# mLRS-tx-dualSx-top-v031.net
KiCad netlist of a schematic drawn in EAGLE
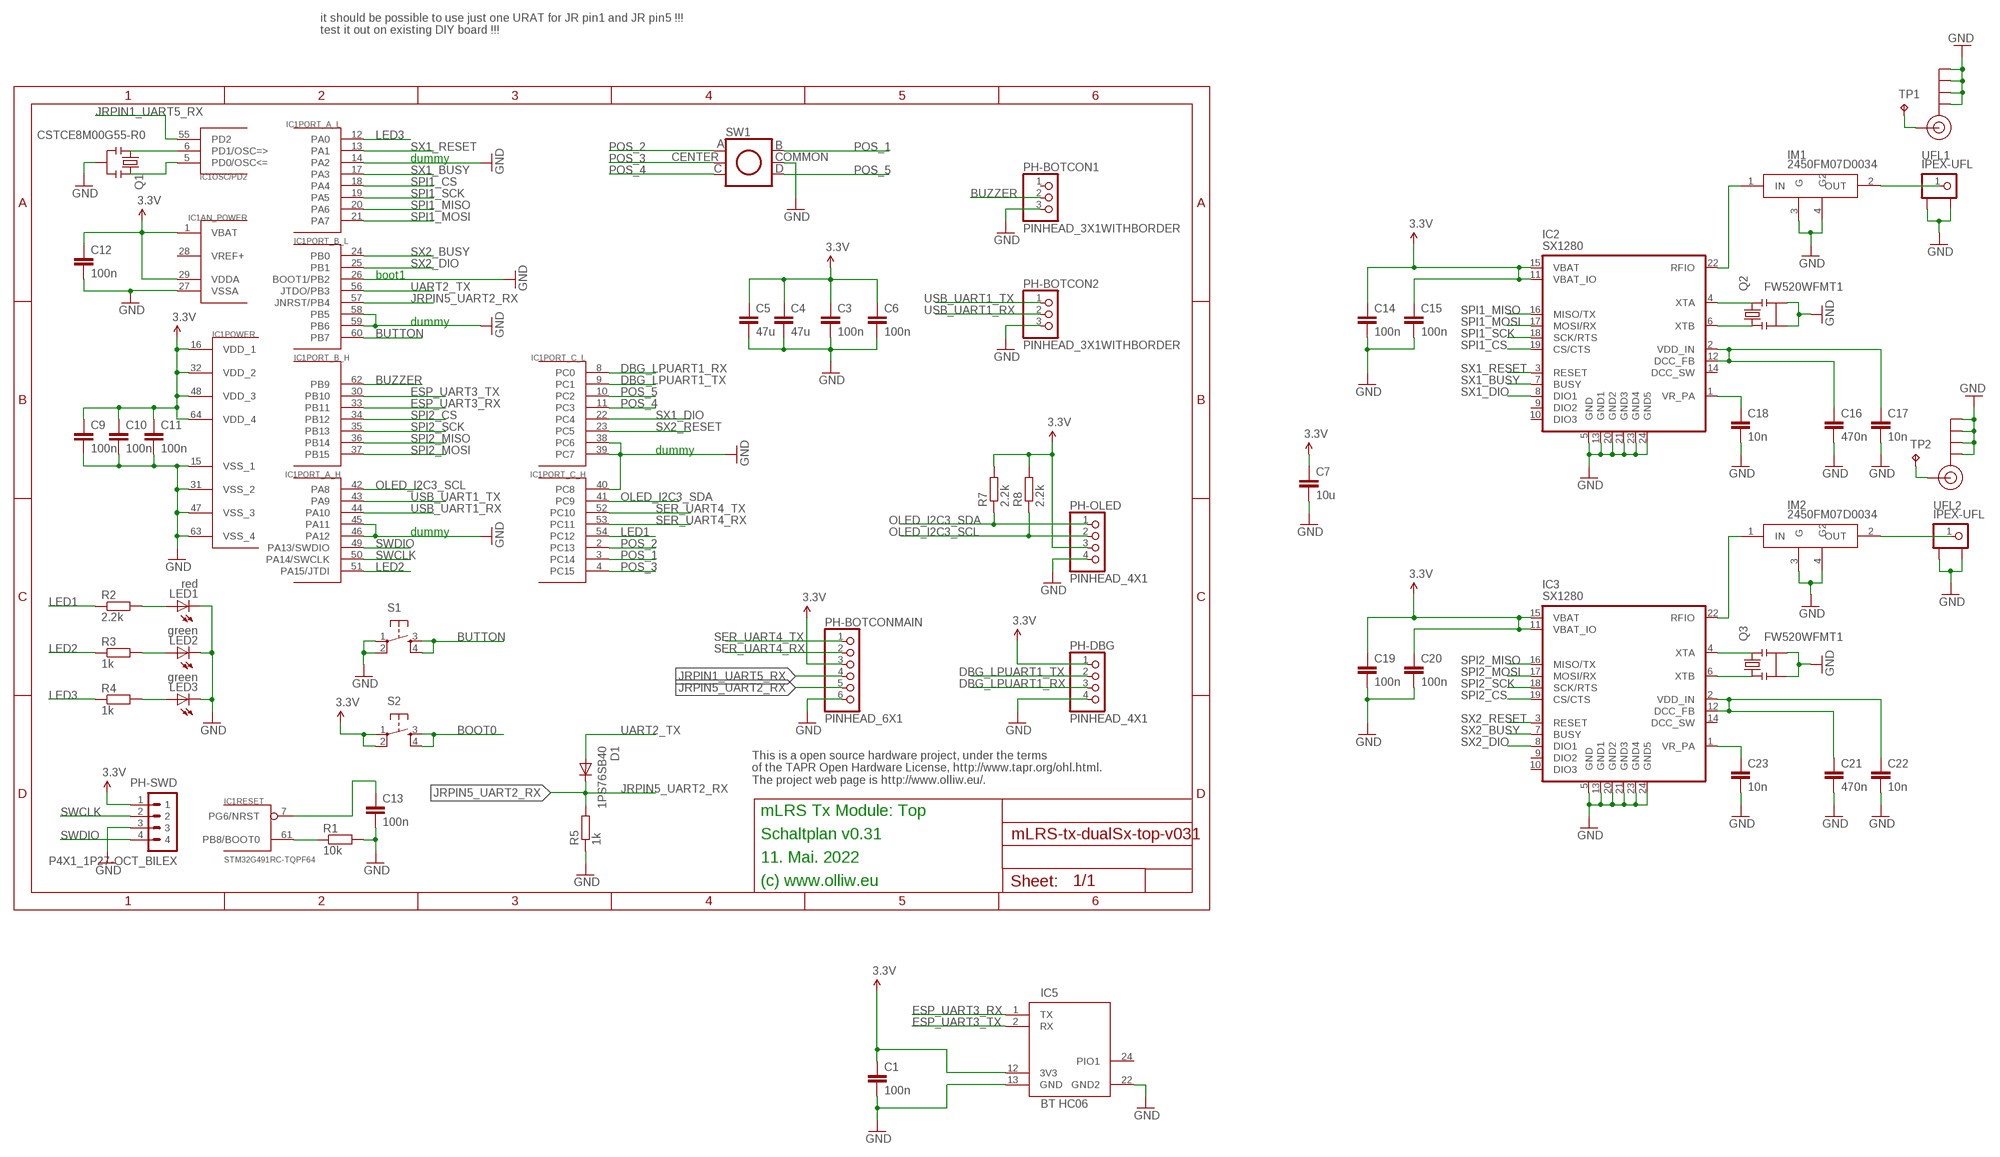
[diagram p0: schematic, sheet 1]

(export (version "E")
  (design (tool "Eeschema 10.0.6"))
  (components
    (comp (ref "C1")
      (value "100n")
      (footprint "eagle-import:C0603")
      (libsource (lib "eagle-import") (part "C-EUC0603"))
    )
    (comp (ref "C3")
      (value "100n")
      (footprint "eagle-import:C0402")
      (libsource (lib "eagle-import") (part "C-EUC0402"))
    )
    (comp (ref "C4")
      (value "47u")
      (footprint "eagle-import:C1210")
      (libsource (lib "eagle-import") (part "C-EUC1210"))
    )
    (comp (ref "C5")
      (value "47u")
      (footprint "eagle-import:C1206K")
      (libsource (lib "eagle-import") (part "C-EUC1206K"))
    )
    (comp (ref "C6")
      (value "100n")
      (footprint "eagle-import:C0402")
      (libsource (lib "eagle-import") (part "C-EUC0402"))
    )
    (comp (ref "C7")
      (value "10u")
      (footprint "eagle-import:C0603")
      (libsource (lib "eagle-import") (part "C-EUC0603"))
    )
    (comp (ref "C9")
      (value "100n")
      (footprint "eagle-import:C0402")
      (libsource (lib "eagle-import") (part "C-EUC0402"))
    )
    (comp (ref "C10")
      (value "100n")
      (footprint "eagle-import:C0402")
      (libsource (lib "eagle-import") (part "C-EUC0402"))
    )
    (comp (ref "C11")
      (value "100n")
      (footprint "eagle-import:C0402")
      (libsource (lib "eagle-import") (part "C-EUC0402"))
    )
    (comp (ref "C12")
      (value "100n")
      (footprint "eagle-import:C0402")
      (libsource (lib "eagle-import") (part "C-EUC0402"))
    )
    (comp (ref "C13")
      (value "100n")
      (footprint "eagle-import:C0402")
      (libsource (lib "eagle-import") (part "C-EUC0402"))
    )
    (comp (ref "C14")
      (value "100n")
      (footprint "eagle-import:C0402")
      (libsource (lib "eagle-import") (part "C-EUC0402"))
    )
    (comp (ref "C15")
      (value "100n")
      (footprint "eagle-import:C0402")
      (libsource (lib "eagle-import") (part "C-EUC0402"))
    )
    (comp (ref "C16")
      (value "470n")
      (footprint "eagle-import:C0402")
      (libsource (lib "eagle-import") (part "C-EUC0402"))
    )
    (comp (ref "C17")
      (value "10n")
      (footprint "eagle-import:C0402")
      (libsource (lib "eagle-import") (part "C-EUC0402"))
    )
    (comp (ref "C18")
      (value "10n")
      (footprint "eagle-import:C0402")
      (libsource (lib "eagle-import") (part "C-EUC0402"))
    )
    (comp (ref "C19")
      (value "100n")
      (footprint "eagle-import:C0402")
      (libsource (lib "eagle-import") (part "C-EUC0402"))
    )
    (comp (ref "C20")
      (value "100n")
      (footprint "eagle-import:C0402")
      (libsource (lib "eagle-import") (part "C-EUC0402"))
    )
    (comp (ref "C21")
      (value "470n")
      (footprint "eagle-import:C0402")
      (libsource (lib "eagle-import") (part "C-EUC0402"))
    )
    (comp (ref "C22")
      (value "10n")
      (footprint "eagle-import:C0402")
      (libsource (lib "eagle-import") (part "C-EUC0402"))
    )
    (comp (ref "C23")
      (value "10n")
      (footprint "eagle-import:C0402")
      (libsource (lib "eagle-import") (part "C-EUC0402"))
    )
    (comp (ref "D1")
      (value "1PS76SB40")
      (footprint "eagle-import:SOD110-R")
      (libsource (lib "eagle-import") (part "DIODE-SOD110-R"))
    )
    (comp (ref "IC1")
      (value "STM32G491RC-TQPF64")
      (footprint "eagle-import:TQFP64")
      (libsource (lib "eagle-import") (part "STM32G4X1RX-TQPF64"))
    )
    (comp (ref "IC2")
      (value "SX1280")
      (footprint "eagle-import:QFN24-4X4-SX128X")
      (libsource (lib "eagle-import") (part "SX1280"))
    )
    (comp (ref "IC3")
      (value "SX1280")
      (footprint "eagle-import:QFN24-4X4-SX128X")
      (libsource (lib "eagle-import") (part "SX1280"))
    )
    (comp (ref "IC5")
      (value "BT HC06")
      (footprint "eagle-import:BT_HC05_BASIC")
      (libsource (lib "eagle-import") (part "HC06-BASIC"))
    )
    (comp (ref "IM1")
      (value "2450FM07D0034")
      (footprint "eagle-import:SX-IMPEDANCE-MATCH")
      (libsource (lib "eagle-import") (part "SX-IMPEDANCE-MATCH"))
    )
    (comp (ref "IM2")
      (value "2450FM07D0034")
      (footprint "eagle-import:SX-IMPEDANCE-MATCH")
      (libsource (lib "eagle-import") (part "SX-IMPEDANCE-MATCH"))
    )
    (comp (ref "LED1")
      (value "red")
      (footprint "eagle-import:CHIPLED_0603")
      (libsource (lib "eagle-import") (part "LEDCHIPLED_0603"))
    )
    (comp (ref "LED2")
      (value "green")
      (footprint "eagle-import:CHIPLED_0603")
      (libsource (lib "eagle-import") (part "LEDCHIPLED_0603"))
    )
    (comp (ref "LED3")
      (value "green")
      (footprint "eagle-import:CHIPLED_0603")
      (libsource (lib "eagle-import") (part "LEDCHIPLED_0603"))
    )
    (comp (ref "PH-BOTCON1")
      (value "PINHEAD_3X1WITHBORDER")
      (footprint "eagle-import:PINHEAD_3X1")
      (libsource (lib "eagle-import") (part "PINHEAD_3X1WITHBORDER"))
    )
    (comp (ref "PH-BOTCON2")
      (value "PINHEAD_3X1WITHBORDER")
      (footprint "eagle-import:PINHEAD_3X1")
      (libsource (lib "eagle-import") (part "PINHEAD_3X1WITHBORDER"))
    )
    (comp (ref "PH-BOTCONMAIN")
      (value "PINHEAD_6X1")
      (footprint "eagle-import:PINHEAD_6X1")
      (libsource (lib "eagle-import") (part "PINHEAD_6X1"))
    )
    (comp (ref "PH-DBG")
      (value "PINHEAD_4X1")
      (footprint "eagle-import:PINHEAD_4X1")
      (libsource (lib "eagle-import") (part "PINHEAD_4X1"))
    )
    (comp (ref "PH-OLED")
      (value "PINHEAD_4X1")
      (footprint "eagle-import:PINHEAD_4X1")
      (libsource (lib "eagle-import") (part "PINHEAD_4X1"))
    )
    (comp (ref "PH-SWD")
      (value "P4X1_1P27-OCT_BILEX")
      (footprint "eagle-import:4X1_1P27_OCT_BILEX")
      (libsource (lib "eagle-import") (part "P4X1_1P27-OCT_BILEX"))
    )
    (comp (ref "Q1")
      (value "CSTCE8M00G55-R0")
      (footprint "eagle-import:RESONATOR-SMD")
      (libsource (lib "eagle-import") (part "RESONATORSMD"))
    )
    (comp (ref "Q2")
      (value "FW520WFMT1")
      (footprint "eagle-import:CRYSTAL-SMD-2X1P6-GND")
      (libsource (lib "eagle-import") (part "CRYSTAL52MHZ"))
    )
    (comp (ref "Q3")
      (value "FW520WFMT1")
      (footprint "eagle-import:CRYSTAL-SMD-2X1P6-GND")
      (libsource (lib "eagle-import") (part "CRYSTAL52MHZ"))
    )
    (comp (ref "R1")
      (value "10k")
      (footprint "eagle-import:R0402")
      (libsource (lib "eagle-import") (part "R-EU_R0402"))
    )
    (comp (ref "R2")
      (value "2.2k")
      (footprint "eagle-import:R0402")
      (libsource (lib "eagle-import") (part "R-EU_R0402"))
    )
    (comp (ref "R3")
      (value "1k")
      (footprint "eagle-import:R0402")
      (libsource (lib "eagle-import") (part "R-EU_R0402"))
    )
    (comp (ref "R4")
      (value "1k")
      (footprint "eagle-import:R0402")
      (libsource (lib "eagle-import") (part "R-EU_R0402"))
    )
    (comp (ref "R5")
      (value "1k")
      (footprint "eagle-import:R0402")
      (libsource (lib "eagle-import") (part "R-EU_R0402"))
    )
    (comp (ref "R7")
      (value "2.2k")
      (footprint "eagle-import:R0402")
      (libsource (lib "eagle-import") (part "R-EU_R0402"))
    )
    (comp (ref "R8")
      (value "2.2k")
      (footprint "eagle-import:R0402")
      (libsource (lib "eagle-import") (part "R-EU_R0402"))
    )
    (comp (ref "RF1")
      (value "SMA_EDGE")
      (footprint "eagle-import:SMA-EDGE")
      (libsource (lib "eagle-import") (part "SMA_EDGE"))
    )
    (comp (ref "RF2")
      (value "SMA_EDGE")
      (footprint "eagle-import:SMA-EDGE")
      (libsource (lib "eagle-import") (part "SMA_EDGE"))
    )
    (comp (ref "S1")
      (value "TAC_SWITCHPTH")
      (footprint "eagle-import:TACTILE-PTH")
      (libsource (lib "eagle-import") (part "TAC_SWITCHPTH"))
    )
    (comp (ref "S2")
      (value "TAC_SWITCHPTH")
      (footprint "eagle-import:TACTILE-PTH")
      (libsource (lib "eagle-import") (part "TAC_SWITCHPTH"))
    )
    (comp (ref "SW1")
      (value "JOYSTICK-5WAY")
      (footprint "eagle-import:JOYSTICK-5WAY")
      (libsource (lib "eagle-import") (part "JOYSTICK-5WAY"))
    )
    (comp (ref "TP1")
      (value "TPTP10SQ")
      (footprint "eagle-import:TP10SQ")
      (libsource (lib "eagle-import") (part "TPTP10SQ"))
    )
    (comp (ref "TP2")
      (value "TPTP10SQ")
      (footprint "eagle-import:TP10SQ")
      (libsource (lib "eagle-import") (part "TPTP10SQ"))
    )
    (comp (ref "UFL1")
      (value "IPEX-UFL")
      (footprint "eagle-import:IPEX-UFL-SMD")
      (libsource (lib "eagle-import") (part "IPEX-UFL"))
    )
    (comp (ref "UFL2")
      (value "IPEX-UFL")
      (footprint "eagle-import:IPEX-UFL-SMD")
      (libsource (lib "eagle-import") (part "IPEX-UFL"))
    )
  )
  (nets
    (net (code "1") (name "/BOOT0") (class "Default")
      (node (ref "IC1") (pin "61") (pinfunction "PB8/BOOT0_61") (pintype "input"))
      (node (ref "R1") (pin "1") (pinfunction "1_1") (pintype "passive"))
      (node (ref "S2") (pin "3") (pinfunction "3_3") (pintype "passive"))
      (node (ref "S2") (pin "4") (pinfunction "4_4") (pintype "passive"))
    )
    (net (code "2") (name "/BUTTON") (class "Default")
      (node (ref "IC1") (pin "60") (pinfunction "PB7_60") (pintype "bidirectional"))
      (node (ref "S1") (pin "3") (pinfunction "3_3") (pintype "passive"))
      (node (ref "S1") (pin "4") (pinfunction "4_4") (pintype "passive"))
    )
    (net (code "3") (name "/BUZZER") (class "Default")
      (node (ref "IC1") (pin "62") (pinfunction "PB9_62") (pintype "bidirectional"))
      (node (ref "PH-BOTCON1") (pin "2") (pinfunction "3_2") (pintype "passive"))
    )
    (net (code "4") (name "/DBG_LPUART1_RX") (class "Default")
      (node (ref "IC1") (pin "8") (pinfunction "PC0_8") (pintype "bidirectional"))
      (node (ref "PH-DBG") (pin "3") (pinfunction "3_3") (pintype "passive"))
    )
    (net (code "5") (name "/DBG_LPUART1_TX") (class "Default")
      (node (ref "IC1") (pin "9") (pinfunction "PC1_9") (pintype "bidirectional"))
      (node (ref "PH-DBG") (pin "2") (pinfunction "2_2") (pintype "passive"))
    )
    (net (code "6") (name "/ESP_UART3_RX") (class "Default")
      (node (ref "IC1") (pin "33") (pinfunction "PB11_33") (pintype "bidirectional"))
      (node (ref "IC5") (pin "1") (pinfunction "TX_1") (pintype "bidirectional"))
    )
    (net (code "7") (name "/ESP_UART3_TX") (class "Default")
      (node (ref "IC1") (pin "30") (pinfunction "PB10_30") (pintype "bidirectional"))
      (node (ref "IC5") (pin "2") (pinfunction "RX_2") (pintype "bidirectional"))
    )
    (net (code "8") (name "/LED1") (class "Default")
      (node (ref "IC1") (pin "54") (pinfunction "PC12_54") (pintype "bidirectional"))
      (node (ref "R2") (pin "1") (pinfunction "1_1") (pintype "passive"))
    )
    (net (code "9") (name "/LED2") (class "Default")
      (node (ref "IC1") (pin "51") (pinfunction "PA15/JTDI_51") (pintype "bidirectional"))
      (node (ref "R3") (pin "1") (pinfunction "1_1") (pintype "passive"))
    )
    (net (code "10") (name "/LED3") (class "Default")
      (node (ref "IC1") (pin "12") (pinfunction "PA0_12") (pintype "bidirectional"))
      (node (ref "R4") (pin "1") (pinfunction "1_1") (pintype "passive"))
    )
    (net (code "11") (name "/OLED_I2C3_SCL") (class "Default")
      (node (ref "IC1") (pin "42") (pinfunction "PA8_42") (pintype "bidirectional"))
      (node (ref "PH-OLED") (pin "2") (pinfunction "2_2") (pintype "passive"))
      (node (ref "R8") (pin "1") (pinfunction "1_1") (pintype "passive"))
    )
    (net (code "12") (name "/OLED_I2C3_SDA") (class "Default")
      (node (ref "IC1") (pin "41") (pinfunction "PC9_41") (pintype "bidirectional"))
      (node (ref "PH-OLED") (pin "1") (pinfunction "1_1") (pintype "passive"))
      (node (ref "R7") (pin "1") (pinfunction "1_1") (pintype "passive"))
    )
    (net (code "13") (name "/POS_1") (class "Default")
      (node (ref "IC1") (pin "3") (pinfunction "PC14_3") (pintype "bidirectional"))
      (node (ref "SW1") (pin "4") (pinfunction "B_4") (pintype "bidirectional"))
    )
    (net (code "14") (name "/POS_2") (class "Default")
      (node (ref "IC1") (pin "2") (pinfunction "PC13_2") (pintype "bidirectional"))
      (node (ref "SW1") (pin "1") (pinfunction "A_1") (pintype "bidirectional"))
    )
    (net (code "15") (name "/POS_3") (class "Default")
      (node (ref "IC1") (pin "4") (pinfunction "PC15_4") (pintype "bidirectional"))
      (node (ref "SW1") (pin "2") (pinfunction "CENTER_2") (pintype "bidirectional"))
    )
    (net (code "16") (name "/POS_4") (class "Default")
      (node (ref "IC1") (pin "11") (pinfunction "PC3_11") (pintype "bidirectional"))
      (node (ref "SW1") (pin "3") (pinfunction "C_3") (pintype "bidirectional"))
    )
    (net (code "17") (name "/POS_5") (class "Default")
      (node (ref "IC1") (pin "10") (pinfunction "PC2_10") (pintype "bidirectional"))
      (node (ref "SW1") (pin "6") (pinfunction "D_6") (pintype "bidirectional"))
    )
    (net (code "18") (name "/SER_UART4_RX") (class "Default")
      (node (ref "IC1") (pin "53") (pinfunction "PC11_53") (pintype "bidirectional"))
      (node (ref "PH-BOTCONMAIN") (pin "2") (pinfunction "2_2") (pintype "passive"))
    )
    (net (code "19") (name "/SER_UART4_TX") (class "Default")
      (node (ref "IC1") (pin "52") (pinfunction "PC10_52") (pintype "bidirectional"))
      (node (ref "PH-BOTCONMAIN") (pin "1") (pinfunction "1_1") (pintype "passive"))
    )
    (net (code "20") (name "/SPI1_CS") (class "Default")
      (node (ref "IC1") (pin "18") (pinfunction "PA4_18") (pintype "bidirectional"))
      (node (ref "IC2") (pin "19") (pinfunction "CS/CTS_19") (pintype "input"))
    )
    (net (code "21") (name "/SPI1_MISO") (class "Default")
      (node (ref "IC1") (pin "20") (pinfunction "PA6_20") (pintype "bidirectional"))
      (node (ref "IC2") (pin "16") (pinfunction "MISO/TX_16") (pintype "input"))
    )
    (net (code "22") (name "/SPI1_MOSI") (class "Default")
      (node (ref "IC1") (pin "21") (pinfunction "PA7_21") (pintype "bidirectional"))
      (node (ref "IC2") (pin "17") (pinfunction "MOSI/RX_17") (pintype "input"))
    )
    (net (code "23") (name "/SPI1_SCK") (class "Default")
      (node (ref "IC1") (pin "19") (pinfunction "PA5_19") (pintype "bidirectional"))
      (node (ref "IC2") (pin "18") (pinfunction "SCK/RTS_18") (pintype "input"))
    )
    (net (code "24") (name "/SPI2_CS") (class "Default")
      (node (ref "IC1") (pin "34") (pinfunction "PB12_34") (pintype "bidirectional"))
      (node (ref "IC3") (pin "19") (pinfunction "CS/CTS_19") (pintype "input"))
    )
    (net (code "25") (name "/SPI2_MISO") (class "Default")
      (node (ref "IC1") (pin "36") (pinfunction "PB14_36") (pintype "bidirectional"))
      (node (ref "IC3") (pin "16") (pinfunction "MISO/TX_16") (pintype "input"))
    )
    (net (code "26") (name "/SPI2_MOSI") (class "Default")
      (node (ref "IC1") (pin "37") (pinfunction "PB15_37") (pintype "bidirectional"))
      (node (ref "IC3") (pin "17") (pinfunction "MOSI/RX_17") (pintype "input"))
    )
    (net (code "27") (name "/SPI2_SCK") (class "Default")
      (node (ref "IC1") (pin "35") (pinfunction "PB13_35") (pintype "bidirectional"))
      (node (ref "IC3") (pin "18") (pinfunction "SCK/RTS_18") (pintype "input"))
    )
    (net (code "28") (name "/SWCLK") (class "Default")
      (node (ref "IC1") (pin "50") (pinfunction "PA14/SWCLK_50") (pintype "bidirectional"))
      (node (ref "PH-SWD") (pin "2") (pinfunction "2_2") (pintype "passive"))
    )
    (net (code "29") (name "/SWDIO") (class "Default")
      (node (ref "IC1") (pin "49") (pinfunction "PA13/SWDIO_49") (pintype "bidirectional"))
      (node (ref "PH-SWD") (pin "4") (pinfunction "4_4") (pintype "passive"))
    )
    (net (code "30") (name "/SX1_BUSY") (class "Default")
      (node (ref "IC1") (pin "17") (pinfunction "PA3_17") (pintype "bidirectional"))
      (node (ref "IC2") (pin "7") (pinfunction "BUSY_7") (pintype "bidirectional"))
    )
    (net (code "31") (name "/SX1_DIO") (class "Default")
      (node (ref "IC1") (pin "22") (pinfunction "PC4_22") (pintype "bidirectional"))
      (node (ref "IC2") (pin "8") (pinfunction "DIO1_8") (pintype "input"))
    )
    (net (code "32") (name "/SX1_RESET") (class "Default")
      (node (ref "IC1") (pin "13") (pinfunction "PA1_13") (pintype "bidirectional"))
      (node (ref "IC2") (pin "3") (pinfunction "RESET_3") (pintype "bidirectional"))
    )
    (net (code "33") (name "/SX2_BUSY") (class "Default")
      (node (ref "IC1") (pin "24") (pinfunction "PB0_24") (pintype "bidirectional"))
      (node (ref "IC3") (pin "7") (pinfunction "BUSY_7") (pintype "bidirectional"))
    )
    (net (code "34") (name "/SX2_DIO") (class "Default")
      (node (ref "IC1") (pin "25") (pinfunction "PB1_25") (pintype "bidirectional"))
      (node (ref "IC3") (pin "8") (pinfunction "DIO1_8") (pintype "input"))
    )
    (net (code "35") (name "/SX2_RESET") (class "Default")
      (node (ref "IC1") (pin "23") (pinfunction "PC5_23") (pintype "bidirectional"))
      (node (ref "IC3") (pin "3") (pinfunction "RESET_3") (pintype "bidirectional"))
    )
    (net (code "36") (name "/UART2_TX") (class "Default")
      (node (ref "D1") (pin "A") (pinfunction "A_A") (pintype "passive"))
      (node (ref "IC1") (pin "56") (pinfunction "JTDO/PB3_56") (pintype "bidirectional"))
    )
    (net (code "37") (name "/USB_UART1_RX") (class "Default")
      (node (ref "IC1") (pin "44") (pinfunction "PA10_44") (pintype "bidirectional"))
      (node (ref "PH-BOTCON2") (pin "2") (pinfunction "3_2") (pintype "passive"))
    )
    (net (code "38") (name "/USB_UART1_TX") (class "Default")
      (node (ref "IC1") (pin "43") (pinfunction "PA9_43") (pintype "bidirectional"))
      (node (ref "PH-BOTCON2") (pin "1") (pinfunction "1_1") (pintype "passive"))
    )
    (net (code "39") (name "3.3V") (class "Default")
      (node (ref "C1") (pin "1") (pinfunction "1_1") (pintype "passive"))
      (node (ref "C10") (pin "1") (pinfunction "1_1") (pintype "passive"))
      (node (ref "C11") (pin "1") (pinfunction "1_1") (pintype "passive"))
      (node (ref "C12") (pin "1") (pinfunction "1_1") (pintype "passive"))
      (node (ref "C14") (pin "1") (pinfunction "1_1") (pintype "passive"))
      (node (ref "C15") (pin "1") (pinfunction "1_1") (pintype "passive"))
      (node (ref "C19") (pin "1") (pinfunction "1_1") (pintype "passive"))
      (node (ref "C20") (pin "1") (pinfunction "1_1") (pintype "passive"))
      (node (ref "C3") (pin "1") (pinfunction "1_1") (pintype "passive"))
      (node (ref "C4") (pin "1") (pinfunction "1_1") (pintype "passive"))
      (node (ref "C5") (pin "1") (pinfunction "1_1") (pintype "passive"))
      (node (ref "C6") (pin "1") (pinfunction "1_1") (pintype "passive"))
      (node (ref "C7") (pin "1") (pinfunction "1_1") (pintype "passive"))
      (node (ref "C9") (pin "1") (pinfunction "1_1") (pintype "passive"))
      (node (ref "IC1") (pin "1") (pinfunction "VBAT_1") (pintype "power_in"))
      (node (ref "IC1") (pin "16") (pinfunction "VDD_1_16") (pintype "power_in"))
      (node (ref "IC1") (pin "29") (pinfunction "VDDA_29") (pintype "power_in"))
      (node (ref "IC1") (pin "32") (pinfunction "VDD_2_32") (pintype "power_in"))
      (node (ref "IC1") (pin "48") (pinfunction "VDD_3_48") (pintype "power_in"))
      (node (ref "IC1") (pin "64") (pinfunction "VDD_4_64") (pintype "power_in"))
      (node (ref "IC2") (pin "11") (pinfunction "VBAT_IO_11") (pintype "power_in"))
      (node (ref "IC2") (pin "15") (pinfunction "VBAT_15") (pintype "power_in"))
      (node (ref "IC3") (pin "11") (pinfunction "VBAT_IO_11") (pintype "power_in"))
      (node (ref "IC3") (pin "15") (pinfunction "VBAT_15") (pintype "power_in"))
      (node (ref "IC5") (pin "12") (pinfunction "3V3_12") (pintype "bidirectional"))
      (node (ref "PH-BOTCONMAIN") (pin "3") (pinfunction "3_3") (pintype "passive"))
      (node (ref "PH-DBG") (pin "1") (pinfunction "1_1") (pintype "passive"))
      (node (ref "PH-OLED") (pin "3") (pinfunction "3_3") (pintype "passive"))
      (node (ref "PH-SWD") (pin "1") (pinfunction "1_1") (pintype "passive"))
      (node (ref "R7") (pin "2") (pinfunction "2_2") (pintype "passive"))
      (node (ref "R8") (pin "2") (pinfunction "2_2") (pintype "passive"))
      (node (ref "S2") (pin "1") (pinfunction "1_1") (pintype "passive"))
      (node (ref "S2") (pin "2") (pinfunction "2_2") (pintype "passive"))
    )
    (net (code "40") (name "GND") (class "Default")
      (node (ref "C1") (pin "2") (pinfunction "2_2") (pintype "passive"))
      (node (ref "C10") (pin "2") (pinfunction "2_2") (pintype "passive"))
      (node (ref "C11") (pin "2") (pinfunction "2_2") (pintype "passive"))
      (node (ref "C12") (pin "2") (pinfunction "2_2") (pintype "passive"))
      (node (ref "C13") (pin "2") (pinfunction "2_2") (pintype "passive"))
      (node (ref "C14") (pin "2") (pinfunction "2_2") (pintype "passive"))
      (node (ref "C15") (pin "2") (pinfunction "2_2") (pintype "passive"))
      (node (ref "C16") (pin "2") (pinfunction "2_2") (pintype "passive"))
      (node (ref "C17") (pin "2") (pinfunction "2_2") (pintype "passive"))
      (node (ref "C18") (pin "2") (pinfunction "2_2") (pintype "passive"))
      (node (ref "C19") (pin "2") (pinfunction "2_2") (pintype "passive"))
      (node (ref "C20") (pin "2") (pinfunction "2_2") (pintype "passive"))
      (node (ref "C21") (pin "2") (pinfunction "2_2") (pintype "passive"))
      (node (ref "C22") (pin "2") (pinfunction "2_2") (pintype "passive"))
      (node (ref "C23") (pin "2") (pinfunction "2_2") (pintype "passive"))
      (node (ref "C3") (pin "2") (pinfunction "2_2") (pintype "passive"))
      (node (ref "C4") (pin "2") (pinfunction "2_2") (pintype "passive"))
      (node (ref "C5") (pin "2") (pinfunction "2_2") (pintype "passive"))
      (node (ref "C6") (pin "2") (pinfunction "2_2") (pintype "passive"))
      (node (ref "C7") (pin "2") (pinfunction "2_2") (pintype "passive"))
      (node (ref "C9") (pin "2") (pinfunction "2_2") (pintype "passive"))
      (node (ref "IC1") (pin "14") (pinfunction "PA2_14") (pintype "bidirectional"))
      (node (ref "IC1") (pin "15") (pinfunction "VSS_1_15") (pintype "power_in"))
      (node (ref "IC1") (pin "26") (pinfunction "BOOT1/PB2_26") (pintype "bidirectional"))
      (node (ref "IC1") (pin "27") (pinfunction "VSSA_27") (pintype "power_in"))
      (node (ref "IC1") (pin "31") (pinfunction "VSS_2_31") (pintype "power_in"))
      (node (ref "IC1") (pin "38") (pinfunction "PC6_38") (pintype "bidirectional"))
      (node (ref "IC1") (pin "39") (pinfunction "PC7_39") (pintype "bidirectional"))
      (node (ref "IC1") (pin "40") (pinfunction "PC8_40") (pintype "bidirectional"))
      (node (ref "IC1") (pin "45") (pinfunction "PA11_45") (pintype "bidirectional"))
      (node (ref "IC1") (pin "46") (pinfunction "PA12_46") (pintype "bidirectional"))
      (node (ref "IC1") (pin "47") (pinfunction "VSS_3_47") (pintype "power_in"))
      (node (ref "IC1") (pin "58") (pinfunction "PB5_58") (pintype "bidirectional"))
      (node (ref "IC1") (pin "59") (pinfunction "PB6_59") (pintype "bidirectional"))
      (node (ref "IC1") (pin "63") (pinfunction "VSS_4_63") (pintype "power_in"))
      (node (ref "IC2") (pin "13") (pinfunction "GND1_13") (pintype "power_in"))
      (node (ref "IC2") (pin "20") (pinfunction "GND2_20") (pintype "power_in"))
      (node (ref "IC2") (pin "21") (pinfunction "GND3_21") (pintype "power_in"))
      (node (ref "IC2") (pin "23") (pinfunction "GND4_23") (pintype "power_in"))
      (node (ref "IC2") (pin "24") (pinfunction "GND5_24") (pintype "power_in"))
      (node (ref "IC2") (pin "5") (pinfunction "GND_5") (pintype "power_in"))
      (node (ref "IC3") (pin "13") (pinfunction "GND1_13") (pintype "power_in"))
      (node (ref "IC3") (pin "20") (pinfunction "GND2_20") (pintype "power_in"))
      (node (ref "IC3") (pin "21") (pinfunction "GND3_21") (pintype "power_in"))
      (node (ref "IC3") (pin "23") (pinfunction "GND4_23") (pintype "power_in"))
      (node (ref "IC3") (pin "24") (pinfunction "GND5_24") (pintype "power_in"))
      (node (ref "IC3") (pin "5") (pinfunction "GND_5") (pintype "power_in"))
      (node (ref "IC5") (pin "13") (pinfunction "GND_13") (pintype "bidirectional"))
      (node (ref "IC5") (pin "22") (pinfunction "GND2_22") (pintype "bidirectional"))
      (node (ref "IM1") (pin "3") (pinfunction "G_3") (pintype "power_in"))
      (node (ref "IM1") (pin "4") (pinfunction "G2_4") (pintype "power_in"))
      (node (ref "IM2") (pin "3") (pinfunction "G_3") (pintype "power_in"))
      (node (ref "IM2") (pin "4") (pinfunction "G2_4") (pintype "power_in"))
      (node (ref "LED1") (pin "C") (pinfunction "C_C") (pintype "passive"))
      (node (ref "LED2") (pin "C") (pinfunction "C_C") (pintype "passive"))
      (node (ref "LED3") (pin "C") (pinfunction "C_C") (pintype "passive"))
      (node (ref "PH-BOTCON1") (pin "3") (pinfunction "5_3") (pintype "passive"))
      (node (ref "PH-BOTCON2") (pin "3") (pinfunction "5_3") (pintype "passive"))
      (node (ref "PH-BOTCONMAIN") (pin "6") (pinfunction "6_6") (pintype "passive"))
      (node (ref "PH-DBG") (pin "4") (pinfunction "4_4") (pintype "passive"))
      (node (ref "PH-OLED") (pin "4") (pinfunction "4_4") (pintype "passive"))
      (node (ref "PH-SWD") (pin "3") (pinfunction "3_3") (pintype "passive"))
      (node (ref "Q1") (pin "2") (pinfunction "2_2") (pintype "passive"))
      (node (ref "Q2") (pin "2") (pinfunction "2_2") (pintype "passive"))
      (node (ref "Q2") (pin "4") (pinfunction "4_4") (pintype "passive"))
      (node (ref "Q3") (pin "2") (pinfunction "2_2") (pintype "passive"))
      (node (ref "Q3") (pin "4") (pinfunction "4_4") (pintype "passive"))
      (node (ref "R1") (pin "2") (pinfunction "2_2") (pintype "passive"))
      (node (ref "R5") (pin "1") (pinfunction "1_1") (pintype "passive"))
      (node (ref "RF1") (pin "GND@0") (pinfunction "GND_GND@0") (pintype "bidirectional"))
      (node (ref "RF1") (pin "GND@1") (pinfunction "GND_GND@1") (pintype "bidirectional"))
      (node (ref "RF1") (pin "GND@2") (pinfunction "GND_GND@2") (pintype "bidirectional"))
      (node (ref "RF1") (pin "GND@3") (pinfunction "GND_GND@3") (pintype "bidirectional"))
      (node (ref "RF2") (pin "GND@0") (pinfunction "GND_GND@0") (pintype "bidirectional"))
      (node (ref "RF2") (pin "GND@1") (pinfunction "GND_GND@1") (pintype "bidirectional"))
      (node (ref "RF2") (pin "GND@2") (pinfunction "GND_GND@2") (pintype "bidirectional"))
      (node (ref "RF2") (pin "GND@3") (pinfunction "GND_GND@3") (pintype "bidirectional"))
      (node (ref "S1") (pin "1") (pinfunction "1_1") (pintype "passive"))
      (node (ref "S1") (pin "2") (pinfunction "2_2") (pintype "passive"))
      (node (ref "SW1") (pin "5") (pinfunction "COMMON_5") (pintype "bidirectional"))
      (node (ref "UFL1") (pin "2") (pinfunction "2_2") (pintype "power_in"))
      (node (ref "UFL1") (pin "3") (pinfunction "3_3") (pintype "power_in"))
      (node (ref "UFL2") (pin "2") (pinfunction "2_2") (pintype "power_in"))
      (node (ref "UFL2") (pin "3") (pinfunction "3_3") (pintype "power_in"))
    )
    (net (code "41") (name "JRPIN1_UART5_RX") (class "Default")
      (node (ref "IC1") (pin "55") (pinfunction "PD2_55") (pintype "bidirectional"))
      (node (ref "PH-BOTCONMAIN") (pin "4") (pinfunction "4_4") (pintype "passive"))
    )
    (net (code "42") (name "JRPIN5_UART2_RX") (class "Default")
      (node (ref "D1") (pin "C") (pinfunction "C_C") (pintype "passive"))
      (node (ref "IC1") (pin "57") (pinfunction "JNRST/PB4_57") (pintype "bidirectional"))
      (node (ref "PH-BOTCONMAIN") (pin "5") (pinfunction "5_5") (pintype "passive"))
      (node (ref "R5") (pin "2") (pinfunction "2_2") (pintype "passive"))
    )
    (net (code "43") (name "Net-(IC1B-PD0{slash}OSC<=)") (class "Default")
      (node (ref "IC1") (pin "5") (pinfunction "PD0/OSC<=_5") (pintype "bidirectional"))
      (node (ref "Q1") (pin "3") (pinfunction "3_3") (pintype "passive"))
    )
    (net (code "44") (name "Net-(IC1B-PD1{slash}OSC=>)") (class "Default")
      (node (ref "IC1") (pin "6") (pinfunction "PD1/OSC=>_6") (pintype "bidirectional"))
      (node (ref "Q1") (pin "1") (pinfunction "1_1") (pintype "passive"))
    )
    (net (code "45") (name "Net-(IC1J-PG6{slash}NRST)") (class "Default")
      (node (ref "C13") (pin "1") (pinfunction "1_1") (pintype "passive"))
      (node (ref "IC1") (pin "7") (pinfunction "PG6/NRST_7") (pintype "input"))
    )
    (net (code "46") (name "Net-(IC2-DCC_FB)") (class "Default")
      (node (ref "C16") (pin "1") (pinfunction "1_1") (pintype "passive"))
      (node (ref "C17") (pin "1") (pinfunction "1_1") (pintype "passive"))
      (node (ref "IC2") (pin "12") (pinfunction "DCC_FB_12") (pintype "bidirectional"))
      (node (ref "IC2") (pin "2") (pinfunction "VDD_IN_2") (pintype "power_in"))
    )
    (net (code "47") (name "Net-(IC2-RFIO)") (class "Default")
      (node (ref "IC2") (pin "22") (pinfunction "RFIO_22") (pintype "bidirectional"))
      (node (ref "IM1") (pin "1") (pinfunction "IN_1") (pintype "bidirectional"))
    )
    (net (code "48") (name "Net-(IC2-VR_PA)") (class "Default")
      (node (ref "C18") (pin "1") (pinfunction "1_1") (pintype "passive"))
      (node (ref "IC2") (pin "1") (pinfunction "VR_PA_1") (pintype "bidirectional"))
    )
    (net (code "49") (name "Net-(IC2-XTA)") (class "Default")
      (node (ref "IC2") (pin "4") (pinfunction "XTA_4") (pintype "bidirectional"))
      (node (ref "Q2") (pin "3") (pinfunction "3_3") (pintype "passive"))
    )
    (net (code "50") (name "Net-(IC2-XTB)") (class "Default")
      (node (ref "IC2") (pin "6") (pinfunction "XTB_6") (pintype "bidirectional"))
      (node (ref "Q2") (pin "1") (pinfunction "1_1") (pintype "passive"))
    )
    (net (code "51") (name "Net-(IC3-DCC_FB)") (class "Default")
      (node (ref "C21") (pin "1") (pinfunction "1_1") (pintype "passive"))
      (node (ref "C22") (pin "1") (pinfunction "1_1") (pintype "passive"))
      (node (ref "IC3") (pin "12") (pinfunction "DCC_FB_12") (pintype "bidirectional"))
      (node (ref "IC3") (pin "2") (pinfunction "VDD_IN_2") (pintype "power_in"))
    )
    (net (code "52") (name "Net-(IC3-RFIO)") (class "Default")
      (node (ref "IC3") (pin "22") (pinfunction "RFIO_22") (pintype "bidirectional"))
      (node (ref "IM2") (pin "1") (pinfunction "IN_1") (pintype "bidirectional"))
    )
    (net (code "53") (name "Net-(IC3-VR_PA)") (class "Default")
      (node (ref "C23") (pin "1") (pinfunction "1_1") (pintype "passive"))
      (node (ref "IC3") (pin "1") (pinfunction "VR_PA_1") (pintype "bidirectional"))
    )
    (net (code "54") (name "Net-(IC3-XTA)") (class "Default")
      (node (ref "IC3") (pin "4") (pinfunction "XTA_4") (pintype "bidirectional"))
      (node (ref "Q3") (pin "3") (pinfunction "3_3") (pintype "passive"))
    )
    (net (code "55") (name "Net-(IC3-XTB)") (class "Default")
      (node (ref "IC3") (pin "6") (pinfunction "XTB_6") (pintype "bidirectional"))
      (node (ref "Q3") (pin "1") (pinfunction "1_1") (pintype "passive"))
    )
    (net (code "56") (name "Net-(IM1-OUT)") (class "Default")
      (node (ref "IM1") (pin "2") (pinfunction "OUT_2") (pintype "bidirectional"))
      (node (ref "UFL1") (pin "1") (pinfunction "1_1") (pintype "passive"))
    )
    (net (code "57") (name "Net-(IM2-OUT)") (class "Default")
      (node (ref "IM2") (pin "2") (pinfunction "OUT_2") (pintype "bidirectional"))
      (node (ref "UFL2") (pin "1") (pinfunction "1_1") (pintype "passive"))
    )
    (net (code "58") (name "Net-(LED1-PadA)") (class "Default")
      (node (ref "LED1") (pin "A") (pinfunction "A_A") (pintype "passive"))
      (node (ref "R2") (pin "2") (pinfunction "2_2") (pintype "passive"))
    )
    (net (code "59") (name "Net-(LED2-PadA)") (class "Default")
      (node (ref "LED2") (pin "A") (pinfunction "A_A") (pintype "passive"))
      (node (ref "R3") (pin "2") (pinfunction "2_2") (pintype "passive"))
    )
    (net (code "60") (name "Net-(LED3-PadA)") (class "Default")
      (node (ref "LED3") (pin "A") (pinfunction "A_A") (pintype "passive"))
      (node (ref "R4") (pin "2") (pinfunction "2_2") (pintype "passive"))
    )
    (net (code "61") (name "Net-(RF1-SIGNAL)") (class "Default")
      (node (ref "RF1") (pin "SIG") (pinfunction "SIGNAL_SIG") (pintype "bidirectional"))
      (node (ref "TP2") (pin "TP") (pinfunction "TP_TP") (pintype "input"))
    )
    (net (code "62") (name "Net-(RF2-SIGNAL)") (class "Default")
      (node (ref "RF2") (pin "SIG") (pinfunction "SIGNAL_SIG") (pintype "bidirectional"))
      (node (ref "TP1") (pin "TP") (pinfunction "TP_TP") (pintype "input"))
    )
    (net (code "63") (name "unconnected-(IC1A-VREF+-Pad28)") (class "Default")
      (node (ref "IC1") (pin "28") (pinfunction "VREF+_28") (pintype "input"))
    )
    (net (code "64") (name "unconnected-(IC2-DCC_SW-Pad14)") (class "Default")
      (node (ref "IC2") (pin "14") (pinfunction "DCC_SW_14") (pintype "bidirectional"))
    )
    (net (code "65") (name "unconnected-(IC2-DIO2-Pad9)") (class "Default")
      (node (ref "IC2") (pin "9") (pinfunction "DIO2_9") (pintype "input"))
    )
    (net (code "66") (name "unconnected-(IC2-DIO3-Pad10)") (class "Default")
      (node (ref "IC2") (pin "10") (pinfunction "DIO3_10") (pintype "input"))
    )
    (net (code "67") (name "unconnected-(IC3-DCC_SW-Pad14)") (class "Default")
      (node (ref "IC3") (pin "14") (pinfunction "DCC_SW_14") (pintype "bidirectional"))
    )
    (net (code "68") (name "unconnected-(IC3-DIO2-Pad9)") (class "Default")
      (node (ref "IC3") (pin "9") (pinfunction "DIO2_9") (pintype "input"))
    )
    (net (code "69") (name "unconnected-(IC3-DIO3-Pad10)") (class "Default")
      (node (ref "IC3") (pin "10") (pinfunction "DIO3_10") (pintype "input"))
    )
    (net (code "70") (name "unconnected-(IC5-PIO1-Pad24)") (class "Default")
      (node (ref "IC5") (pin "24") (pinfunction "PIO1_24") (pintype "bidirectional"))
    )
    (net (code "71") (name "unconnected-(PH-BOTCON1-Pad1)") (class "Default")
      (node (ref "PH-BOTCON1") (pin "1") (pinfunction "1_1") (pintype "passive"))
    )
  )
)
